# Multipler.net
KiCad netlist of a schematic drawn in Altium Designer
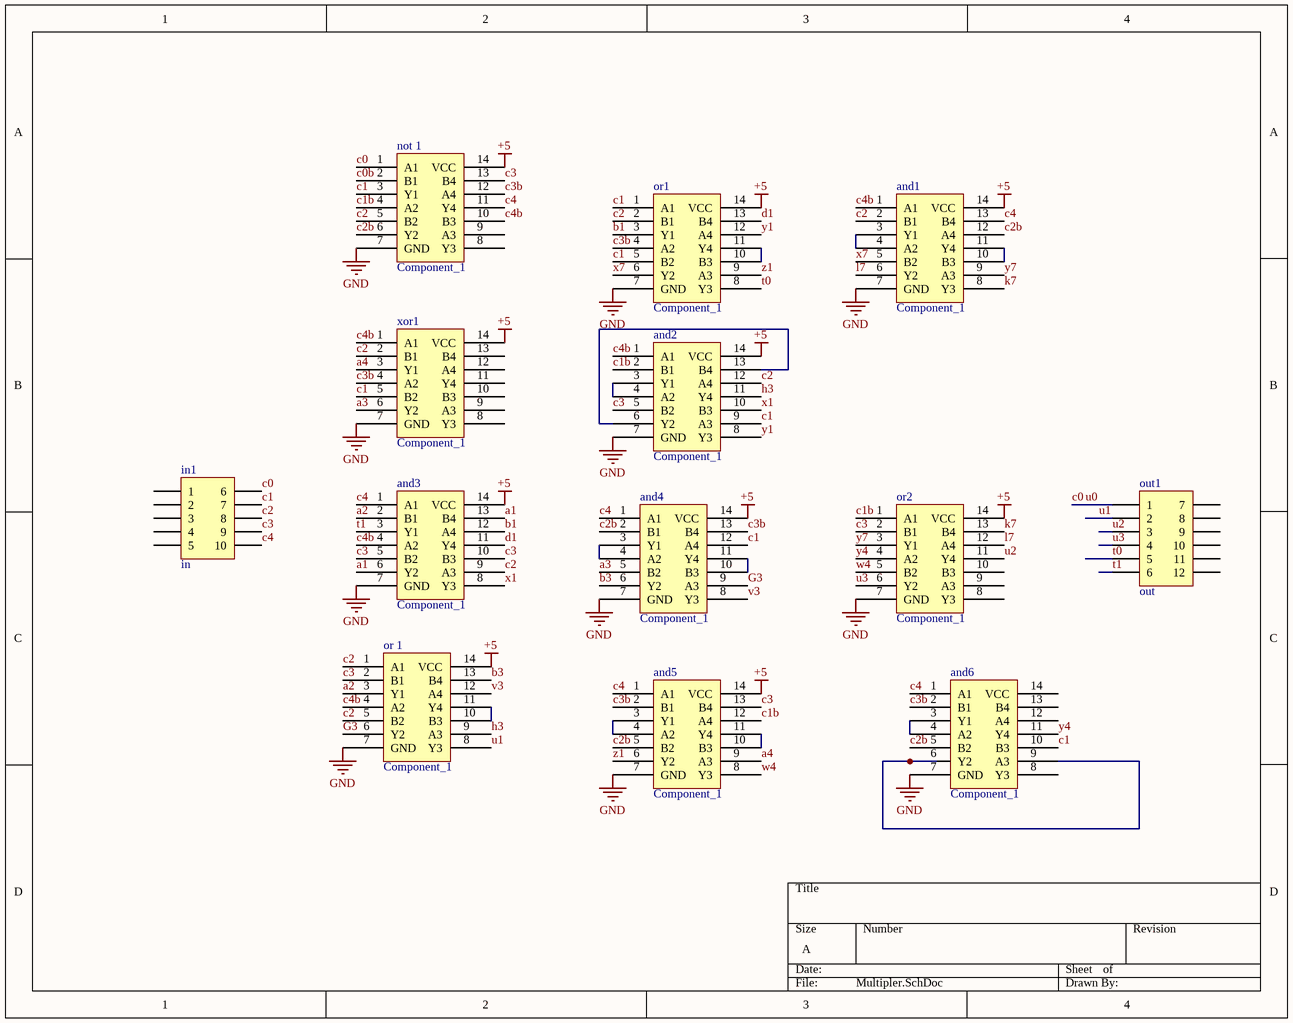
[diagram p0: Multipler.SchDoc]

(export (version "E")
  (design (tool "Eeschema 10.0.6"))
  (components
    (comp (ref "and1")
      (value "Component_1")
      (footprint "and gate:PCBComponent_1")
      (libsource (lib "and schemetic") (part "Component_1"))
    )
    (comp (ref "and2")
      (value "Component_1")
      (footprint "and gate:PCBComponent_1")
      (libsource (lib "and schemetic") (part "Component_1"))
    )
    (comp (ref "and3")
      (value "Component_1")
      (footprint "and gate:PCBComponent_1")
      (libsource (lib "and schemetic") (part "Component_1"))
    )
    (comp (ref "and4")
      (value "Component_1")
      (footprint "and gate:PCBComponent_1")
      (libsource (lib "and schemetic") (part "Component_1"))
    )
    (comp (ref "and5")
      (value "Component_1")
      (footprint "and gate:PCBComponent_1")
      (libsource (lib "and schemetic") (part "Component_1"))
    )
    (comp (ref "and6")
      (value "Component_1")
      (footprint "and gate:PCBComponent_1")
      (libsource (lib "and schemetic") (part "Component_1"))
    )
    (comp (ref "in1")
      (value "in")
      (footprint "HDR2X5_CEN")
      (description "Header, 5-Pin, Dual row")
      (fields (field (name "PUBLISHER") "Altium Limited"))
      (libsource (lib "Miscellaneous Connectors") (part "Header 5X2A"))
    )
    (comp (ref "not 1")
      (value "Component_1")
      (footprint "and gate:PCBComponent_1")
      (libsource (lib "and schemetic") (part "Component_1"))
    )
    (comp (ref "or 1")
      (value "Component_1")
      (footprint "and gate:PCBComponent_1")
      (libsource (lib "and schemetic") (part "Component_1"))
    )
    (comp (ref "or1")
      (value "Component_1")
      (footprint "and gate:PCBComponent_1")
      (libsource (lib "and schemetic") (part "Component_1"))
    )
    (comp (ref "or2")
      (value "Component_1")
      (footprint "and gate:PCBComponent_1")
      (libsource (lib "and schemetic") (part "Component_1"))
    )
    (comp (ref "out1")
      (value "out")
      (footprint "HDR2X6_CEN")
      (description "Header, 6-Pin, Dual row")
      (fields (field (name "PUBLISHER") "Altium Limited"))
      (libsource (lib "Miscellaneous Connectors") (part "Header 6X2A"))
    )
    (comp (ref "xor1")
      (value "Component_1")
      (footprint "and gate:PCBComponent_1")
      (libsource (lib "and schemetic") (part "Component_1"))
    )
  )
  (nets
    (net (code "1") (name "+5") (class "Default")
      (node (ref "and1") (pin "14") (pinfunction "VCC_14") (pintype "passive"))
      (node (ref "and2") (pin "14") (pinfunction "VCC_14") (pintype "passive"))
      (node (ref "and3") (pin "14") (pinfunction "VCC_14") (pintype "passive"))
      (node (ref "and4") (pin "14") (pinfunction "VCC_14") (pintype "passive"))
      (node (ref "and5") (pin "14") (pinfunction "VCC_14") (pintype "passive"))
      (node (ref "not 1") (pin "14") (pinfunction "VCC_14") (pintype "passive"))
      (node (ref "or 1") (pin "14") (pinfunction "VCC_14") (pintype "passive"))
      (node (ref "or1") (pin "14") (pinfunction "VCC_14") (pintype "passive"))
      (node (ref "or2") (pin "14") (pinfunction "VCC_14") (pintype "passive"))
      (node (ref "xor1") (pin "14") (pinfunction "VCC_14") (pintype "passive"))
    )
    (net (code "2") (name "/G3") (class "Default")
      (node (ref "and4") (pin "9") (pinfunction "A3_9") (pintype "passive"))
      (node (ref "or 1") (pin "6") (pinfunction "Y2_6") (pintype "passive"))
    )
    (net (code "3") (name "/a1") (class "Default")
      (node (ref "and3") (pin "13") (pinfunction "B4_13") (pintype "passive"))
      (node (ref "and3") (pin "6") (pinfunction "Y2_6") (pintype "passive"))
    )
    (net (code "4") (name "/a2") (class "Default")
      (node (ref "and3") (pin "2") (pinfunction "B1_2") (pintype "passive"))
      (node (ref "or 1") (pin "3") (pinfunction "Y1_3") (pintype "passive"))
    )
    (net (code "5") (name "/a3") (class "Default")
      (node (ref "and4") (pin "5") (pinfunction "B2_5") (pintype "passive"))
      (node (ref "xor1") (pin "6") (pinfunction "Y2_6") (pintype "passive"))
    )
    (net (code "6") (name "/a4") (class "Default")
      (node (ref "and5") (pin "9") (pinfunction "A3_9") (pintype "passive"))
      (node (ref "xor1") (pin "3") (pinfunction "Y1_3") (pintype "passive"))
    )
    (net (code "7") (name "/b1") (class "Default")
      (node (ref "and3") (pin "12") (pinfunction "A4_12") (pintype "passive"))
      (node (ref "or1") (pin "3") (pinfunction "Y1_3") (pintype "passive"))
    )
    (net (code "8") (name "/b3") (class "Default")
      (node (ref "and4") (pin "6") (pinfunction "Y2_6") (pintype "passive"))
      (node (ref "or 1") (pin "13") (pinfunction "B4_13") (pintype "passive"))
    )
    (net (code "9") (name "/c0") (class "Default")
      (node (ref "in1") (pin "6") (pinfunction "6_6") (pintype "passive"))
      (node (ref "not 1") (pin "1") (pinfunction "A1_1") (pintype "passive"))
      (node (ref "out1") (pin "1") (pinfunction "1_1") (pintype "passive"))
    )
    (net (code "10") (name "/c0b") (class "Default")
      (node (ref "not 1") (pin "2") (pinfunction "B1_2") (pintype "passive"))
    )
    (net (code "11") (name "/c1") (class "Default")
      (node (ref "and2") (pin "9") (pinfunction "A3_9") (pintype "passive"))
      (node (ref "and4") (pin "12") (pinfunction "A4_12") (pintype "passive"))
      (node (ref "and6") (pin "10") (pinfunction "B3_10") (pintype "passive"))
      (node (ref "in1") (pin "7") (pinfunction "7_7") (pintype "passive"))
      (node (ref "not 1") (pin "3") (pinfunction "Y1_3") (pintype "passive"))
      (node (ref "or1") (pin "1") (pinfunction "A1_1") (pintype "passive"))
      (node (ref "or1") (pin "5") (pinfunction "B2_5") (pintype "passive"))
      (node (ref "xor1") (pin "5") (pinfunction "B2_5") (pintype "passive"))
    )
    (net (code "12") (name "/c1b") (class "Default")
      (node (ref "and2") (pin "2") (pinfunction "B1_2") (pintype "passive"))
      (node (ref "and5") (pin "12") (pinfunction "A4_12") (pintype "passive"))
      (node (ref "not 1") (pin "4") (pinfunction "A2_4") (pintype "passive"))
      (node (ref "or2") (pin "1") (pinfunction "A1_1") (pintype "passive"))
    )
    (net (code "13") (name "/c2") (class "Default")
      (node (ref "and1") (pin "2") (pinfunction "B1_2") (pintype "passive"))
      (node (ref "and2") (pin "12") (pinfunction "A4_12") (pintype "passive"))
      (node (ref "and3") (pin "9") (pinfunction "A3_9") (pintype "passive"))
      (node (ref "in1") (pin "8") (pinfunction "8_8") (pintype "passive"))
      (node (ref "not 1") (pin "5") (pinfunction "B2_5") (pintype "passive"))
      (node (ref "or 1") (pin "1") (pinfunction "A1_1") (pintype "passive"))
      (node (ref "or 1") (pin "5") (pinfunction "B2_5") (pintype "passive"))
      (node (ref "or1") (pin "2") (pinfunction "B1_2") (pintype "passive"))
      (node (ref "xor1") (pin "2") (pinfunction "B1_2") (pintype "passive"))
    )
    (net (code "14") (name "/c2b") (class "Default")
      (node (ref "and1") (pin "12") (pinfunction "A4_12") (pintype "passive"))
      (node (ref "and4") (pin "2") (pinfunction "B1_2") (pintype "passive"))
      (node (ref "and5") (pin "5") (pinfunction "B2_5") (pintype "passive"))
      (node (ref "and6") (pin "5") (pinfunction "B2_5") (pintype "passive"))
      (node (ref "not 1") (pin "6") (pinfunction "Y2_6") (pintype "passive"))
    )
    (net (code "15") (name "/c3") (class "Default")
      (node (ref "and2") (pin "5") (pinfunction "B2_5") (pintype "passive"))
      (node (ref "and3") (pin "10") (pinfunction "B3_10") (pintype "passive"))
      (node (ref "and3") (pin "5") (pinfunction "B2_5") (pintype "passive"))
      (node (ref "and5") (pin "13") (pinfunction "B4_13") (pintype "passive"))
      (node (ref "in1") (pin "9") (pinfunction "9_9") (pintype "passive"))
      (node (ref "not 1") (pin "13") (pinfunction "B4_13") (pintype "passive"))
      (node (ref "or 1") (pin "2") (pinfunction "B1_2") (pintype "passive"))
      (node (ref "or2") (pin "2") (pinfunction "B1_2") (pintype "passive"))
    )
    (net (code "16") (name "/c3b") (class "Default")
      (node (ref "and4") (pin "13") (pinfunction "B4_13") (pintype "passive"))
      (node (ref "and5") (pin "2") (pinfunction "B1_2") (pintype "passive"))
      (node (ref "and6") (pin "2") (pinfunction "B1_2") (pintype "passive"))
      (node (ref "not 1") (pin "12") (pinfunction "A4_12") (pintype "passive"))
      (node (ref "or1") (pin "4") (pinfunction "A2_4") (pintype "passive"))
      (node (ref "xor1") (pin "4") (pinfunction "A2_4") (pintype "passive"))
    )
    (net (code "17") (name "/c4") (class "Default")
      (node (ref "and1") (pin "13") (pinfunction "B4_13") (pintype "passive"))
      (node (ref "and3") (pin "1") (pinfunction "A1_1") (pintype "passive"))
      (node (ref "and4") (pin "1") (pinfunction "A1_1") (pintype "passive"))
      (node (ref "and5") (pin "1") (pinfunction "A1_1") (pintype "passive"))
      (node (ref "and6") (pin "1") (pinfunction "A1_1") (pintype "passive"))
      (node (ref "in1") (pin "10") (pinfunction "10_10") (pintype "passive"))
      (node (ref "not 1") (pin "11") (pinfunction "Y4_11") (pintype "passive"))
    )
    (net (code "18") (name "/c4b") (class "Default")
      (node (ref "and1") (pin "1") (pinfunction "A1_1") (pintype "passive"))
      (node (ref "and2") (pin "1") (pinfunction "A1_1") (pintype "passive"))
      (node (ref "and3") (pin "4") (pinfunction "A2_4") (pintype "passive"))
      (node (ref "not 1") (pin "10") (pinfunction "B3_10") (pintype "passive"))
      (node (ref "or 1") (pin "4") (pinfunction "A2_4") (pintype "passive"))
      (node (ref "xor1") (pin "1") (pinfunction "A1_1") (pintype "passive"))
    )
    (net (code "19") (name "/d1") (class "Default")
      (node (ref "and3") (pin "11") (pinfunction "Y4_11") (pintype "passive"))
      (node (ref "or1") (pin "13") (pinfunction "B4_13") (pintype "passive"))
    )
    (net (code "20") (name "/h3") (class "Default")
      (node (ref "and2") (pin "11") (pinfunction "Y4_11") (pintype "passive"))
      (node (ref "or 1") (pin "9") (pinfunction "A3_9") (pintype "passive"))
    )
    (net (code "21") (name "/k7") (class "Default")
      (node (ref "and1") (pin "8") (pinfunction "Y3_8") (pintype "passive"))
      (node (ref "or2") (pin "13") (pinfunction "B4_13") (pintype "passive"))
    )
    (net (code "22") (name "/l7") (class "Default")
      (node (ref "and1") (pin "6") (pinfunction "Y2_6") (pintype "passive"))
      (node (ref "or2") (pin "12") (pinfunction "A4_12") (pintype "passive"))
    )
    (net (code "23") (name "/t0") (class "Default")
      (node (ref "or1") (pin "8") (pinfunction "Y3_8") (pintype "passive"))
      (node (ref "out1") (pin "5") (pinfunction "5_5") (pintype "passive"))
    )
    (net (code "24") (name "/t1") (class "Default")
      (node (ref "and3") (pin "3") (pinfunction "Y1_3") (pintype "passive"))
      (node (ref "out1") (pin "6") (pinfunction "6_6") (pintype "passive"))
    )
    (net (code "25") (name "/u1") (class "Default")
      (node (ref "or 1") (pin "8") (pinfunction "Y3_8") (pintype "passive"))
      (node (ref "out1") (pin "2") (pinfunction "2_2") (pintype "passive"))
    )
    (net (code "26") (name "/u2") (class "Default")
      (node (ref "or2") (pin "11") (pinfunction "Y4_11") (pintype "passive"))
      (node (ref "out1") (pin "3") (pinfunction "3_3") (pintype "passive"))
    )
    (net (code "27") (name "/u3") (class "Default")
      (node (ref "or2") (pin "6") (pinfunction "Y2_6") (pintype "passive"))
      (node (ref "out1") (pin "4") (pinfunction "4_4") (pintype "passive"))
    )
    (net (code "28") (name "/v3") (class "Default")
      (node (ref "and4") (pin "8") (pinfunction "Y3_8") (pintype "passive"))
      (node (ref "or 1") (pin "12") (pinfunction "A4_12") (pintype "passive"))
    )
    (net (code "29") (name "/w4") (class "Default")
      (node (ref "and5") (pin "8") (pinfunction "Y3_8") (pintype "passive"))
      (node (ref "or2") (pin "5") (pinfunction "B2_5") (pintype "passive"))
    )
    (net (code "30") (name "/x1") (class "Default")
      (node (ref "and2") (pin "10") (pinfunction "B3_10") (pintype "passive"))
      (node (ref "and3") (pin "8") (pinfunction "Y3_8") (pintype "passive"))
    )
    (net (code "31") (name "/x7") (class "Default")
      (node (ref "and1") (pin "5") (pinfunction "B2_5") (pintype "passive"))
      (node (ref "or1") (pin "6") (pinfunction "Y2_6") (pintype "passive"))
    )
    (net (code "32") (name "/y1") (class "Default")
      (node (ref "and2") (pin "8") (pinfunction "Y3_8") (pintype "passive"))
      (node (ref "or1") (pin "12") (pinfunction "A4_12") (pintype "passive"))
    )
    (net (code "33") (name "/y4") (class "Default")
      (node (ref "and6") (pin "11") (pinfunction "Y4_11") (pintype "passive"))
      (node (ref "or2") (pin "4") (pinfunction "A2_4") (pintype "passive"))
    )
    (net (code "34") (name "/y7") (class "Default")
      (node (ref "and1") (pin "9") (pinfunction "A3_9") (pintype "passive"))
      (node (ref "or2") (pin "3") (pinfunction "Y1_3") (pintype "passive"))
    )
    (net (code "35") (name "/z1") (class "Default")
      (node (ref "and5") (pin "6") (pinfunction "Y2_6") (pintype "passive"))
      (node (ref "or1") (pin "9") (pinfunction "A3_9") (pintype "passive"))
    )
    (net (code "36") (name "GND") (class "Default")
      (node (ref "and1") (pin "7") (pinfunction "GND_7") (pintype "passive"))
      (node (ref "and2") (pin "7") (pinfunction "GND_7") (pintype "passive"))
      (node (ref "and3") (pin "7") (pinfunction "GND_7") (pintype "passive"))
      (node (ref "and4") (pin "7") (pinfunction "GND_7") (pintype "passive"))
      (node (ref "and5") (pin "7") (pinfunction "GND_7") (pintype "passive"))
      (node (ref "and6") (pin "7") (pinfunction "GND_7") (pintype "passive"))
      (node (ref "not 1") (pin "7") (pinfunction "GND_7") (pintype "passive"))
      (node (ref "or 1") (pin "7") (pinfunction "GND_7") (pintype "passive"))
      (node (ref "or1") (pin "7") (pinfunction "GND_7") (pintype "passive"))
      (node (ref "or2") (pin "7") (pinfunction "GND_7") (pintype "passive"))
      (node (ref "xor1") (pin "7") (pinfunction "GND_7") (pintype "passive"))
    )
    (net (code "37") (name "Net-(and1-A2)") (class "Default")
      (node (ref "and1") (pin "3") (pinfunction "Y1_3") (pintype "passive"))
      (node (ref "and1") (pin "4") (pinfunction "A2_4") (pintype "passive"))
    )
    (net (code "38") (name "Net-(and1-B3)") (class "Default")
      (node (ref "and1") (pin "10") (pinfunction "B3_10") (pintype "passive"))
      (node (ref "and1") (pin "11") (pinfunction "Y4_11") (pintype "passive"))
    )
    (net (code "39") (name "Net-(and2-A2)") (class "Default")
      (node (ref "and2") (pin "3") (pinfunction "Y1_3") (pintype "passive"))
      (node (ref "and2") (pin "4") (pinfunction "A2_4") (pintype "passive"))
    )
    (net (code "40") (name "Net-(and2-B4)") (class "Default")
      (node (ref "and2") (pin "13") (pinfunction "B4_13") (pintype "passive"))
      (node (ref "and2") (pin "6") (pinfunction "Y2_6") (pintype "passive"))
    )
    (net (code "41") (name "Net-(and4-A2)") (class "Default")
      (node (ref "and4") (pin "3") (pinfunction "Y1_3") (pintype "passive"))
      (node (ref "and4") (pin "4") (pinfunction "A2_4") (pintype "passive"))
    )
    (net (code "42") (name "Net-(and4-B3)") (class "Default")
      (node (ref "and4") (pin "10") (pinfunction "B3_10") (pintype "passive"))
      (node (ref "and4") (pin "11") (pinfunction "Y4_11") (pintype "passive"))
    )
    (net (code "43") (name "Net-(and5-A2)") (class "Default")
      (node (ref "and5") (pin "3") (pinfunction "Y1_3") (pintype "passive"))
      (node (ref "and5") (pin "4") (pinfunction "A2_4") (pintype "passive"))
    )
    (net (code "44") (name "Net-(and5-B3)") (class "Default")
      (node (ref "and5") (pin "10") (pinfunction "B3_10") (pintype "passive"))
      (node (ref "and5") (pin "11") (pinfunction "Y4_11") (pintype "passive"))
    )
    (net (code "45") (name "Net-(and6-A2)") (class "Default")
      (node (ref "and6") (pin "3") (pinfunction "Y1_3") (pintype "passive"))
      (node (ref "and6") (pin "4") (pinfunction "A2_4") (pintype "passive"))
    )
    (net (code "46") (name "Net-(and6-A3)") (class "Default")
      (node (ref "and6") (pin "6") (pinfunction "Y2_6") (pintype "passive"))
      (node (ref "and6") (pin "9") (pinfunction "A3_9") (pintype "passive"))
    )
    (net (code "47") (name "Net-(or 1-B3)") (class "Default")
      (node (ref "or 1") (pin "10") (pinfunction "B3_10") (pintype "passive"))
      (node (ref "or 1") (pin "11") (pinfunction "Y4_11") (pintype "passive"))
    )
    (net (code "48") (name "Net-(or1-B3)") (class "Default")
      (node (ref "or1") (pin "10") (pinfunction "B3_10") (pintype "passive"))
      (node (ref "or1") (pin "11") (pinfunction "Y4_11") (pintype "passive"))
    )
    (net (code "49") (name "unconnected-(and6-A4-Pad12)") (class "Default")
      (node (ref "and6") (pin "12") (pinfunction "A4_12") (pintype "passive"))
    )
    (net (code "50") (name "unconnected-(and6-B4-Pad13)") (class "Default")
      (node (ref "and6") (pin "13") (pinfunction "B4_13") (pintype "passive"))
    )
    (net (code "51") (name "unconnected-(and6-VCC-Pad14)") (class "Default")
      (node (ref "and6") (pin "14") (pinfunction "VCC_14") (pintype "passive"))
    )
    (net (code "52") (name "unconnected-(and6-Y3-Pad8)") (class "Default")
      (node (ref "and6") (pin "8") (pinfunction "Y3_8") (pintype "passive"))
    )
    (net (code "53") (name "unconnected-(in1-Pad1)") (class "Default")
      (node (ref "in1") (pin "1") (pinfunction "1_1") (pintype "passive"))
    )
    (net (code "54") (name "unconnected-(in1-Pad2)") (class "Default")
      (node (ref "in1") (pin "2") (pinfunction "2_2") (pintype "passive"))
    )
    (net (code "55") (name "unconnected-(in1-Pad3)") (class "Default")
      (node (ref "in1") (pin "3") (pinfunction "3_3") (pintype "passive"))
    )
    (net (code "56") (name "unconnected-(in1-Pad4)") (class "Default")
      (node (ref "in1") (pin "4") (pinfunction "4_4") (pintype "passive"))
    )
    (net (code "57") (name "unconnected-(in1-Pad5)") (class "Default")
      (node (ref "in1") (pin "5") (pinfunction "5_5") (pintype "passive"))
    )
    (net (code "58") (name "unconnected-(not 1-A3-Pad9)") (class "Default")
      (node (ref "not 1") (pin "9") (pinfunction "A3_9") (pintype "passive"))
    )
    (net (code "59") (name "unconnected-(not 1-Y3-Pad8)") (class "Default")
      (node (ref "not 1") (pin "8") (pinfunction "Y3_8") (pintype "passive"))
    )
    (net (code "60") (name "unconnected-(or2-A3-Pad9)") (class "Default")
      (node (ref "or2") (pin "9") (pinfunction "A3_9") (pintype "passive"))
    )
    (net (code "61") (name "unconnected-(or2-B3-Pad10)") (class "Default")
      (node (ref "or2") (pin "10") (pinfunction "B3_10") (pintype "passive"))
    )
    (net (code "62") (name "unconnected-(or2-Y3-Pad8)") (class "Default")
      (node (ref "or2") (pin "8") (pinfunction "Y3_8") (pintype "passive"))
    )
    (net (code "63") (name "unconnected-(out1-Pad7)") (class "Default")
      (node (ref "out1") (pin "7") (pinfunction "7_7") (pintype "passive"))
    )
    (net (code "64") (name "unconnected-(out1-Pad8)") (class "Default")
      (node (ref "out1") (pin "8") (pinfunction "8_8") (pintype "passive"))
    )
    (net (code "65") (name "unconnected-(out1-Pad9)") (class "Default")
      (node (ref "out1") (pin "9") (pinfunction "9_9") (pintype "passive"))
    )
    (net (code "66") (name "unconnected-(out1-Pad10)") (class "Default")
      (node (ref "out1") (pin "10") (pinfunction "10_10") (pintype "passive"))
    )
    (net (code "67") (name "unconnected-(out1-Pad11)") (class "Default")
      (node (ref "out1") (pin "11") (pinfunction "11_11") (pintype "passive"))
    )
    (net (code "68") (name "unconnected-(out1-Pad12)") (class "Default")
      (node (ref "out1") (pin "12") (pinfunction "12_12") (pintype "passive"))
    )
    (net (code "69") (name "unconnected-(xor1-A3-Pad9)") (class "Default")
      (node (ref "xor1") (pin "9") (pinfunction "A3_9") (pintype "passive"))
    )
    (net (code "70") (name "unconnected-(xor1-A4-Pad12)") (class "Default")
      (node (ref "xor1") (pin "12") (pinfunction "A4_12") (pintype "passive"))
    )
    (net (code "71") (name "unconnected-(xor1-B3-Pad10)") (class "Default")
      (node (ref "xor1") (pin "10") (pinfunction "B3_10") (pintype "passive"))
    )
    (net (code "72") (name "unconnected-(xor1-B4-Pad13)") (class "Default")
      (node (ref "xor1") (pin "13") (pinfunction "B4_13") (pintype "passive"))
    )
    (net (code "73") (name "unconnected-(xor1-Y3-Pad8)") (class "Default")
      (node (ref "xor1") (pin "8") (pinfunction "Y3_8") (pintype "passive"))
    )
    (net (code "74") (name "unconnected-(xor1-Y4-Pad11)") (class "Default")
      (node (ref "xor1") (pin "11") (pinfunction "Y4_11") (pintype "passive"))
    )
  )
)
